# BatteryControl.net
KiCad netlist of a schematic drawn in Altium Designer
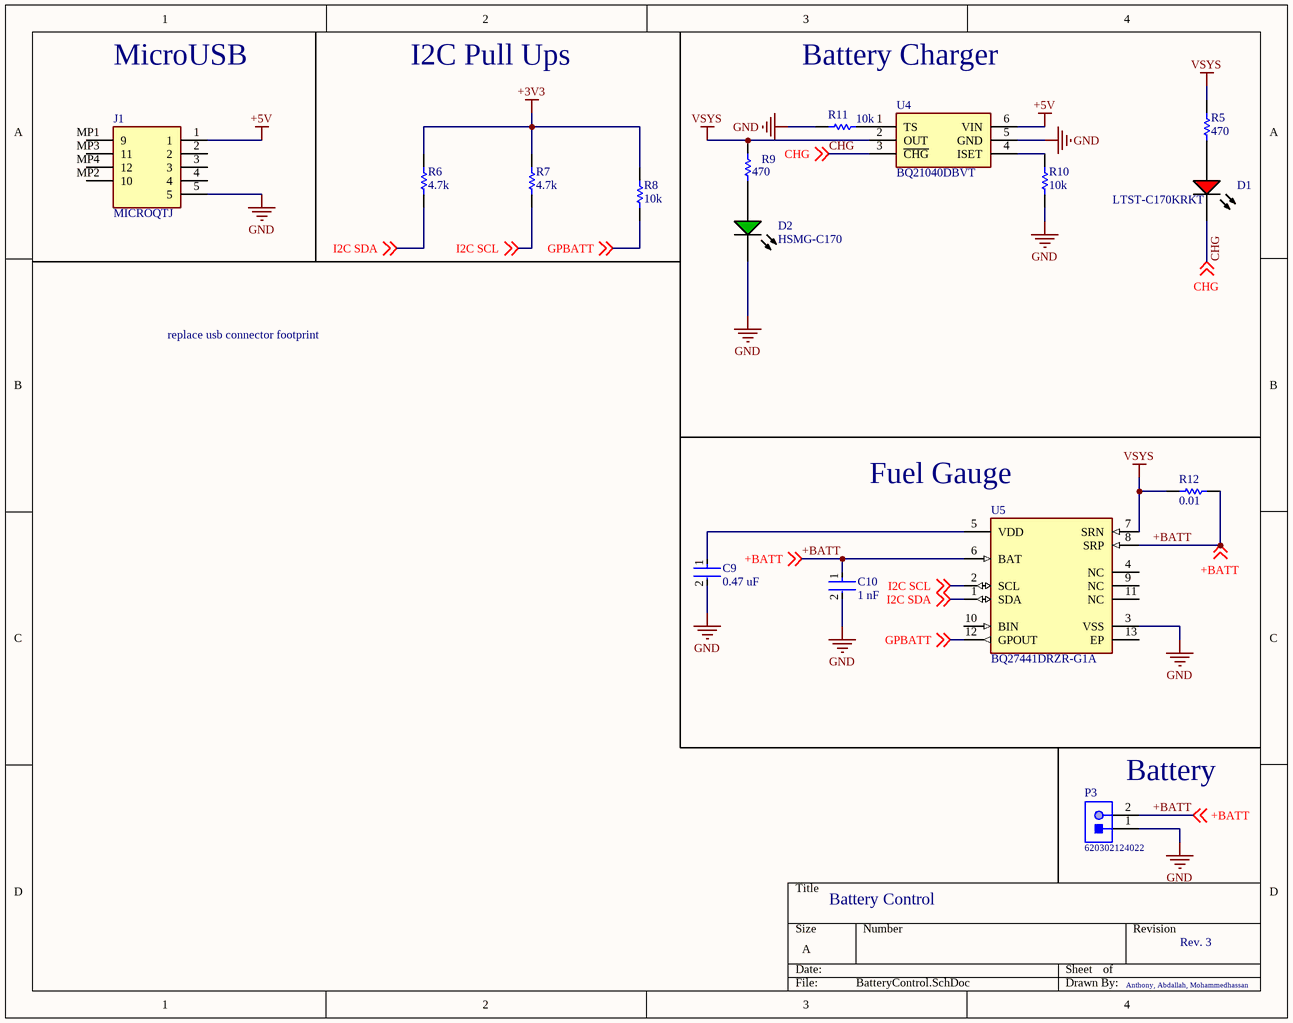
[diagram p0: BatteryControl.SchDoc]

(export (version "E")
  (design (tool "Eeschema 10.0.6"))
  (components
    (comp (ref "C9")
      (value "0.47 uF")
      (footprint "FP-C0805C-DG-MFG")
      (description "CAP CER 10UF 10V X5R 0805")
      (fields (field (name "TOLERANCE") "10%") (field (name "MANUFACTURER PART NUMBER") "C0805C106K8PACTU"))
      (libsource (lib "Altium Content Vault") (part "11868f565c42a9108669ba33697ecf6"))
    )
    (comp (ref "C10")
      (value "1 nF")
      (footprint "FP-C0805C-DG-MFG")
      (description "CAP CER 10UF 10V X5R 0805")
      (fields (field (name "TOLERANCE") "10%") (field (name "MANUFACTURER PART NUMBER") "C0805C106K8PACTU"))
      (libsource (lib "Altium Content Vault") (part "11868f565c42a9108669ba33697ecf6"))
    )
    (comp (ref "D1")
      (value "LTST-C170KRKT")
      (footprint "LTST-C170KRKT_V")
      (description "LED Red, 75 mW, 54 mcd, -55 to 85 degC, 2-Pin SMD, RoHS, Tape and Reel\r\nLCSC Part # C94868")
      (fields (field (name "MANUFACTURER") "Lite-On"))
      (libsource (lib "Altium Content Vault") (part "LED-RED-AK-2"))
    )
    (comp (ref "D2")
      (value "HSMG-C170")
      (footprint "AVAG-HSMX-C170_V")
      (description "Chip LED, Green, 2.2 V, -40 to 85 degC, 2-Pin SMD, Pb-Free, Tape and Reel\r\nLCSC Part # C188728")
      (fields (field (name "MANUFACTURER") "Avago"))
      (libsource (lib "Altium Content Vault") (part "LED_GREEN_A1K2-2"))
    )
    (comp (ref "J1")
      (value "MICROQTJ")
      (footprint "SamacSys:MICROQTJ")
      (description "Connector\r\nLCSC Part # C404968")
      (libsource (lib "*") (part "MICROQTJ"))
    )
    (comp (ref "P3")
      (value "620302124022")
      (footprint "620302124022")
      (fields (field (name "MANUFACTURER") "Wurth Elektronik") (field (name "PUBLISHER") "WurthElektronik"))
      (libsource (lib "Altium Content Vault") (part "WE-CN-1P-M-R2"))
    )
    (comp (ref "R5")
      (value "470")
      (footprint "RESC2013X70X40ML20T20")
      (description "Chip Resistor, 1 KOhm, +/- 1%, 0.125 W, -55 to 155 degC, 0805 (2013 Metric)")
      (fields (field (name "POWER") "125mW") (field (name "TOLERANCE") "1%"))
      (libsource (lib "Formula Racing at UC Davis") (part "RES-2"))
    )
    (comp (ref "R6")
      (value "4.7k")
      (footprint "RESC2013X70X40ML20T20")
      (description "Chip Resistor, 1 KOhm, +/- 1%, 0.125 W, -55 to 155 degC, 0805 (2013 Metric)")
      (fields (field (name "POWER") "125mW") (field (name "TOLERANCE") "1%"))
      (libsource (lib "Formula Racing at UC Davis") (part "RES-2"))
    )
    (comp (ref "R7")
      (value "4.7k")
      (footprint "RESC2013X70X40ML20T20")
      (description "Chip Resistor, 1 KOhm, +/- 1%, 0.125 W, -55 to 155 degC, 0805 (2013 Metric)")
      (fields (field (name "POWER") "125mW") (field (name "TOLERANCE") "1%"))
      (libsource (lib "Formula Racing at UC Davis") (part "RES-2"))
    )
    (comp (ref "R8")
      (value "10k")
      (footprint "RESC2013X70X40ML20T20")
      (description "Chip Resistor, 1 KOhm, +/- 1%, 0.125 W, -55 to 155 degC, 0805 (2013 Metric)")
      (fields (field (name "POWER") "125mW") (field (name "TOLERANCE") "1%"))
      (libsource (lib "Formula Racing at UC Davis") (part "RES-2"))
    )
    (comp (ref "R9")
      (value "470")
      (footprint "RESC2013X70X40ML20T20")
      (description "Chip Resistor, 1 KOhm, +/- 1%, 0.125 W, -55 to 155 degC, 0805 (2013 Metric)")
      (fields (field (name "POWER") "125mW") (field (name "TOLERANCE") "1%"))
      (libsource (lib "Formula Racing at UC Davis") (part "RES-2"))
    )
    (comp (ref "R10")
      (value "10k")
      (footprint "RESC2013X70X40ML20T20")
      (description "Chip Resistor, 1 KOhm, +/- 1%, 0.125 W, -55 to 155 degC, 0805 (2013 Metric)")
      (fields (field (name "POWER") "125mW") (field (name "TOLERANCE") "1%"))
      (libsource (lib "Formula Racing at UC Davis") (part "RES-2"))
    )
    (comp (ref "R11")
      (value "10k")
      (footprint "RESC2013X70X40ML20T20")
      (description "Chip Resistor, 1 KOhm, +/- 1%, 0.125 W, -55 to 155 degC, 0805 (2013 Metric)")
      (fields (field (name "POWER") "125mW") (field (name "TOLERANCE") "1%"))
      (libsource (lib "Formula Racing at UC Davis") (part "RES-2"))
    )
    (comp (ref "R12")
      (value "0.01")
      (footprint "RESC2013X70X40ML20T20")
      (description "Chip Resistor, 1 KOhm, +/- 1%, 0.125 W, -55 to 155 degC, 0805 (2013 Metric)")
      (fields (field (name "POWER") "125mW") (field (name "TOLERANCE") "1%"))
      (libsource (lib "Formula Racing at UC Davis") (part "RES-2"))
    )
    (comp (ref "U4")
      (value "BQ21040DBVT")
      (footprint "SamacSys:SOT95P280X145-6N")
      (description "Integrated Circuit\r\nLCSC Part # C78978")
      (fields (field (name "MOUSER PART NUMBER") "595-BQ21040DBVT"))
      (libsource (lib "*") (part "BQ21040DBVT"))
    )
    (comp (ref "U5")
      (value "BQ27441DRZR-G1A")
      (footprint "FP-DRZ0012A-MFG")
      (description "IC BATT FUEL GAUGE LI-ION 12SON\r\nWON'T BE POPULATED BY MANUFACTURER")
      (fields
        (field (name "OCTOPART") "https://octopart.com/bq27441drzr-g1a-texas+instruments-30555829")
        (field (name "MANUFACTURER") "Texas Instruments")
      )
      (libsource (lib "Altium Content Vault") (part "0f562f18464a1f07b55dcd927f1fdf2"))
    )
  )
  (nets
    (net (code "1") (name "+3V3") (class "Default")
      (node (ref "R6") (pin "2") (pinfunction "2_2") (pintype "passive"))
      (node (ref "R7") (pin "2") (pinfunction "2_2") (pintype "passive"))
      (node (ref "R8") (pin "2") (pinfunction "2_2") (pintype "passive"))
    )
    (net (code "2") (name "+5V") (class "Default")
      (node (ref "J1") (pin "1") (pinfunction "1_1") (pintype "passive"))
      (node (ref "U4") (pin "6") (pinfunction "VIN_6") (pintype "passive"))
    )
    (net (code "3") (name "+BATT") (class "Default")
      (node (ref "C10") (pin "1") (pinfunction "1_1") (pintype "passive"))
      (node (ref "P3") (pin "2") (pinfunction "2_2") (pintype "passive"))
      (node (ref "R12") (pin "1") (pinfunction "1_1") (pintype "passive"))
      (node (ref "U5") (pin "6") (pinfunction "BAT_6") (pintype "input"))
      (node (ref "U5") (pin "8") (pinfunction "SRP_8") (pintype "input"))
    )
    (net (code "4") (name "CHG") (class "Default")
      (node (ref "D1") (pin "2") (pinfunction "K_2") (pintype "passive"))
      (node (ref "U4") (pin "3") (pinfunction "~{CHG}_3") (pintype "passive"))
    )
    (net (code "5") (name "GND") (class "Default")
      (node (ref "C10") (pin "2") (pinfunction "2_2") (pintype "passive"))
      (node (ref "C9") (pin "2") (pinfunction "2_2") (pintype "passive"))
      (node (ref "D2") (pin "2") (pinfunction "K_2") (pintype "passive"))
      (node (ref "J1") (pin "5") (pinfunction "5_5") (pintype "passive"))
      (node (ref "P3") (pin "1") (pinfunction "1_1") (pintype "passive"))
      (node (ref "R10") (pin "2") (pinfunction "2_2") (pintype "passive"))
      (node (ref "R11") (pin "2") (pinfunction "2_2") (pintype "passive"))
      (node (ref "U4") (pin "5") (pinfunction "GND_5") (pintype "passive"))
      (node (ref "U5") (pin "3") (pinfunction "VSS_3") (pintype "power_in"))
    )
    (net (code "6") (name "GPBATT") (class "Default")
      (node (ref "R8") (pin "1") (pinfunction "1_1") (pintype "passive"))
      (node (ref "U5") (pin "12") (pinfunction "GPOUT_12") (pintype "output"))
    )
    (net (code "7") (name "I2C SCL") (class "Default")
      (node (ref "R7") (pin "1") (pinfunction "1_1") (pintype "passive"))
      (node (ref "U5") (pin "2") (pinfunction "SCL_2") (pintype "bidirectional"))
    )
    (net (code "8") (name "I2C SDA") (class "Default")
      (node (ref "R6") (pin "1") (pinfunction "1_1") (pintype "passive"))
      (node (ref "U5") (pin "1") (pinfunction "SDA_1") (pintype "bidirectional"))
    )
    (net (code "9") (name "Net-(D1-A)") (class "Default")
      (node (ref "D1") (pin "1") (pinfunction "A_1") (pintype "passive"))
      (node (ref "R5") (pin "1") (pinfunction "1_1") (pintype "passive"))
    )
    (net (code "10") (name "Net-(D2-A)") (class "Default")
      (node (ref "D2") (pin "1") (pinfunction "A_1") (pintype "passive"))
      (node (ref "R9") (pin "1") (pinfunction "1_1") (pintype "passive"))
    )
    (net (code "11") (name "Net-(U4-ISET)") (class "Default")
      (node (ref "R10") (pin "1") (pinfunction "1_1") (pintype "passive"))
      (node (ref "U4") (pin "4") (pinfunction "ISET_4") (pintype "passive"))
    )
    (net (code "12") (name "Net-(U4-TS)") (class "Default")
      (node (ref "R11") (pin "1") (pinfunction "1_1") (pintype "passive"))
      (node (ref "U4") (pin "1") (pinfunction "TS_1") (pintype "passive"))
    )
    (net (code "13") (name "Net-(U5-VDD)") (class "Default")
      (node (ref "C9") (pin "1") (pinfunction "1_1") (pintype "passive"))
      (node (ref "U5") (pin "5") (pinfunction "VDD_5") (pintype "power_in"))
    )
    (net (code "14") (name "VSYS") (class "Default")
      (node (ref "R12") (pin "2") (pinfunction "2_2") (pintype "passive"))
      (node (ref "R5") (pin "2") (pinfunction "2_2") (pintype "passive"))
      (node (ref "R9") (pin "2") (pinfunction "2_2") (pintype "passive"))
      (node (ref "U4") (pin "2") (pinfunction "OUT_2") (pintype "passive"))
      (node (ref "U5") (pin "7") (pinfunction "SRN_7") (pintype "input"))
    )
    (net (code "15") (name "unconnected-(J1-9-PadMP1)") (class "Default")
      (node (ref "J1") (pin "MP1") (pinfunction "9_MP1") (pintype "passive"))
    )
    (net (code "16") (name "unconnected-(J1-10-PadMP2)") (class "Default")
      (node (ref "J1") (pin "MP2") (pinfunction "10_MP2") (pintype "passive"))
    )
    (net (code "17") (name "unconnected-(J1-11-PadMP3)") (class "Default")
      (node (ref "J1") (pin "MP3") (pinfunction "11_MP3") (pintype "passive"))
    )
    (net (code "18") (name "unconnected-(J1-12-PadMP4)") (class "Default")
      (node (ref "J1") (pin "MP4") (pinfunction "12_MP4") (pintype "passive"))
    )
    (net (code "19") (name "unconnected-(J1-Pad2)") (class "Default")
      (node (ref "J1") (pin "2") (pinfunction "2_2") (pintype "passive"))
    )
    (net (code "20") (name "unconnected-(J1-Pad3)") (class "Default")
      (node (ref "J1") (pin "3") (pinfunction "3_3") (pintype "passive"))
    )
    (net (code "21") (name "unconnected-(J1-Pad4)") (class "Default")
      (node (ref "J1") (pin "4") (pinfunction "4_4") (pintype "passive"))
    )
    (net (code "22") (name "unconnected-(U5-BIN-Pad10)") (class "Default")
      (node (ref "U5") (pin "10") (pinfunction "BIN_10") (pintype "input"))
    )
    (net (code "23") (name "unconnected-(U5-EP-Pad13)") (class "Default")
      (node (ref "U5") (pin "13") (pinfunction "EP_13") (pintype "power_in"))
    )
    (net (code "24") (name "unconnected-(U5-NC-Pad4)") (class "Default")
      (node (ref "U5") (pin "4") (pinfunction "NC_4") (pintype "passive"))
    )
    (net (code "25") (name "unconnected-(U5-NC-Pad9)") (class "Default")
      (node (ref "U5") (pin "9") (pinfunction "NC_9") (pintype "passive"))
    )
    (net (code "26") (name "unconnected-(U5-NC-Pad11)") (class "Default")
      (node (ref "U5") (pin "11") (pinfunction "NC_11") (pintype "passive"))
    )
  )
)
